# 05-multimodal-analogfrontend.net
KiCad netlist of a schematic drawn in Altium Designer
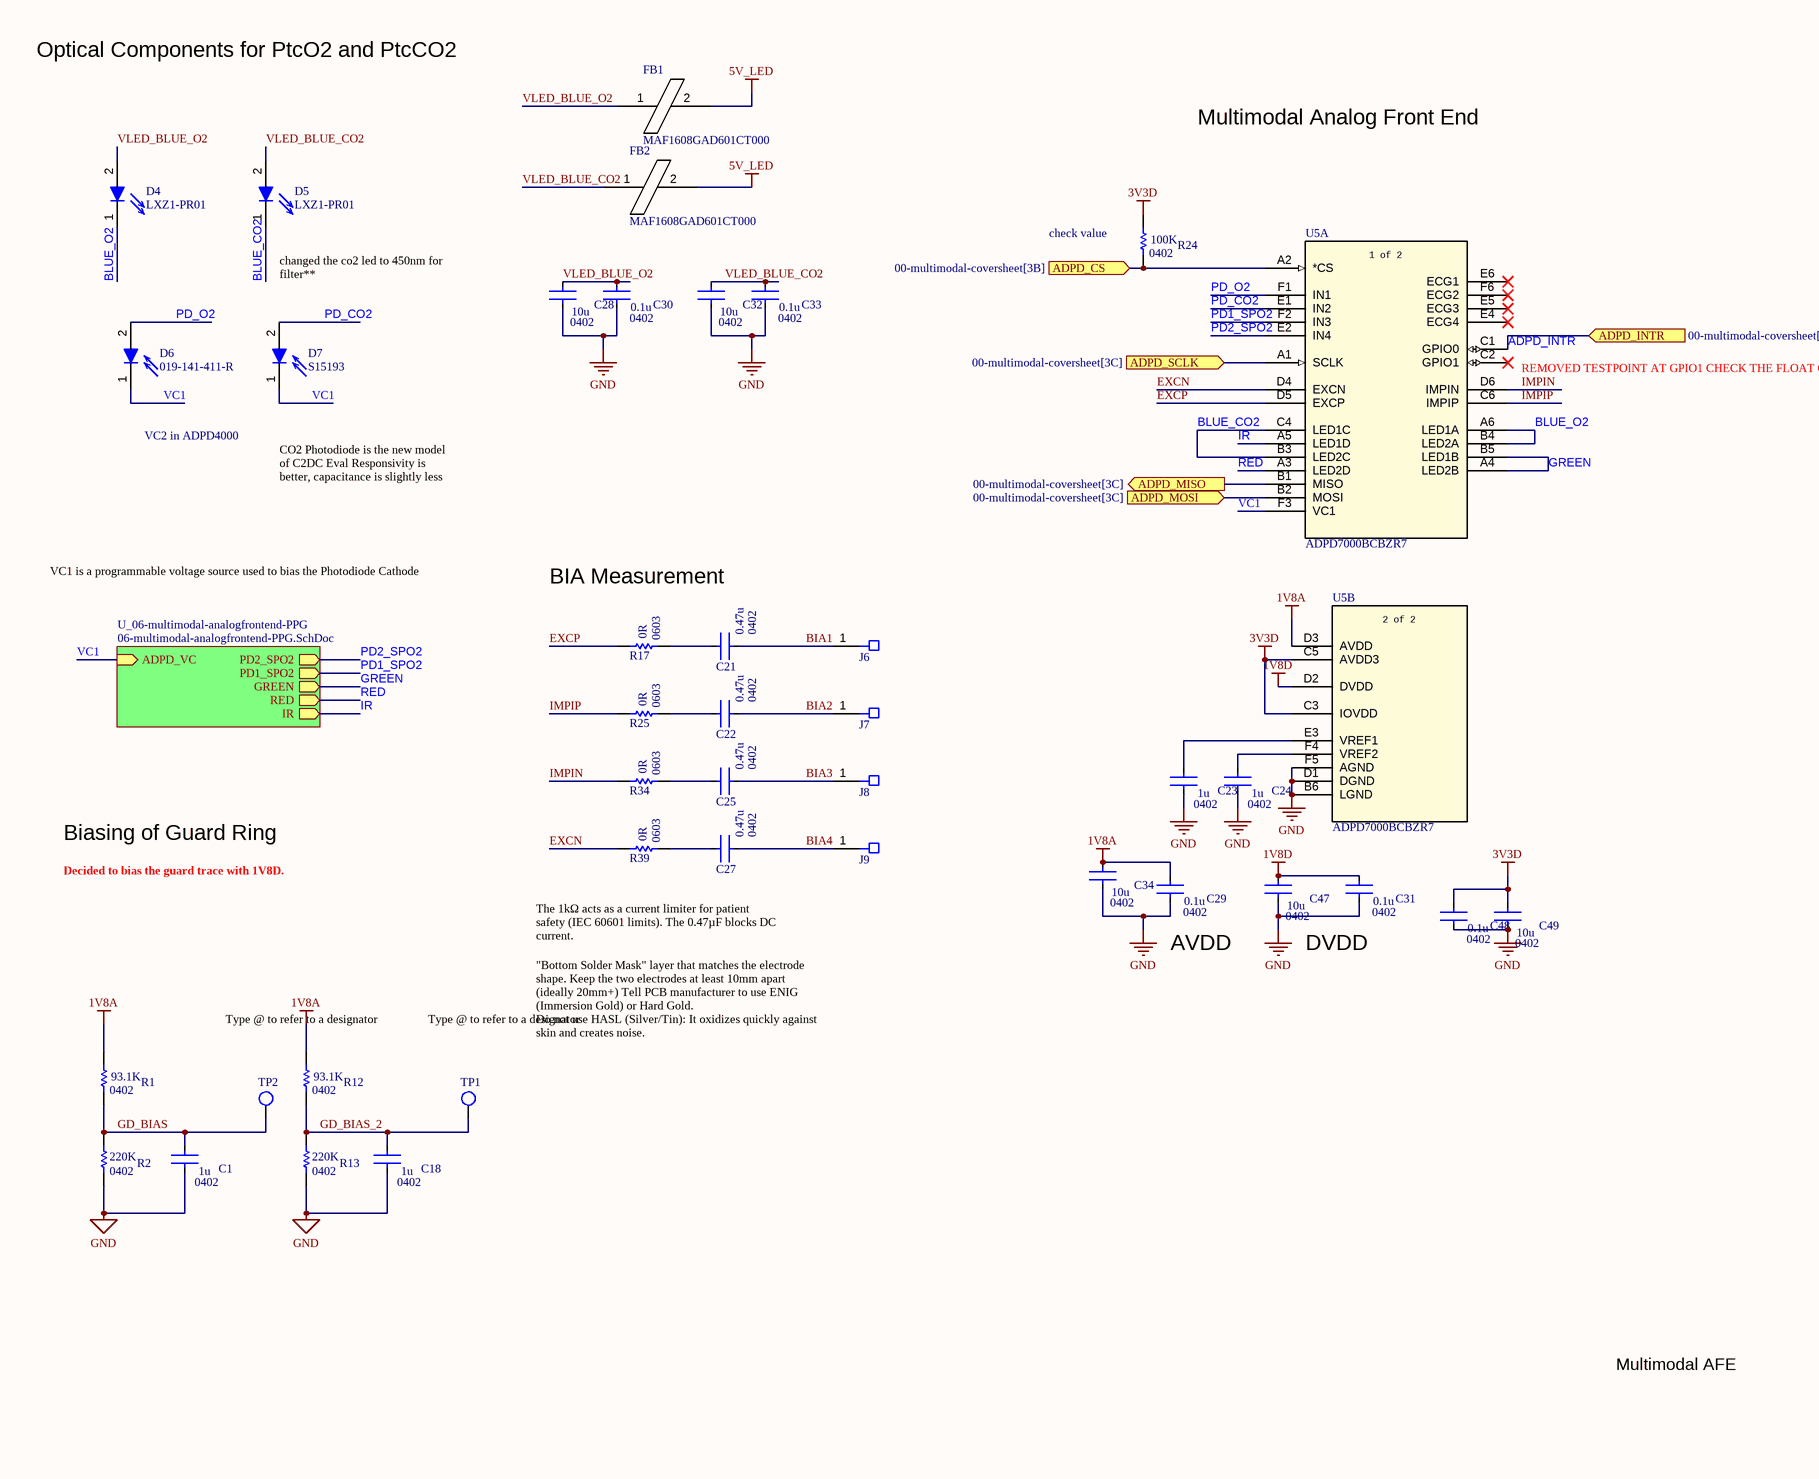
[diagram p0: 05-multimodal-analogfrontend.SchDoc, left]
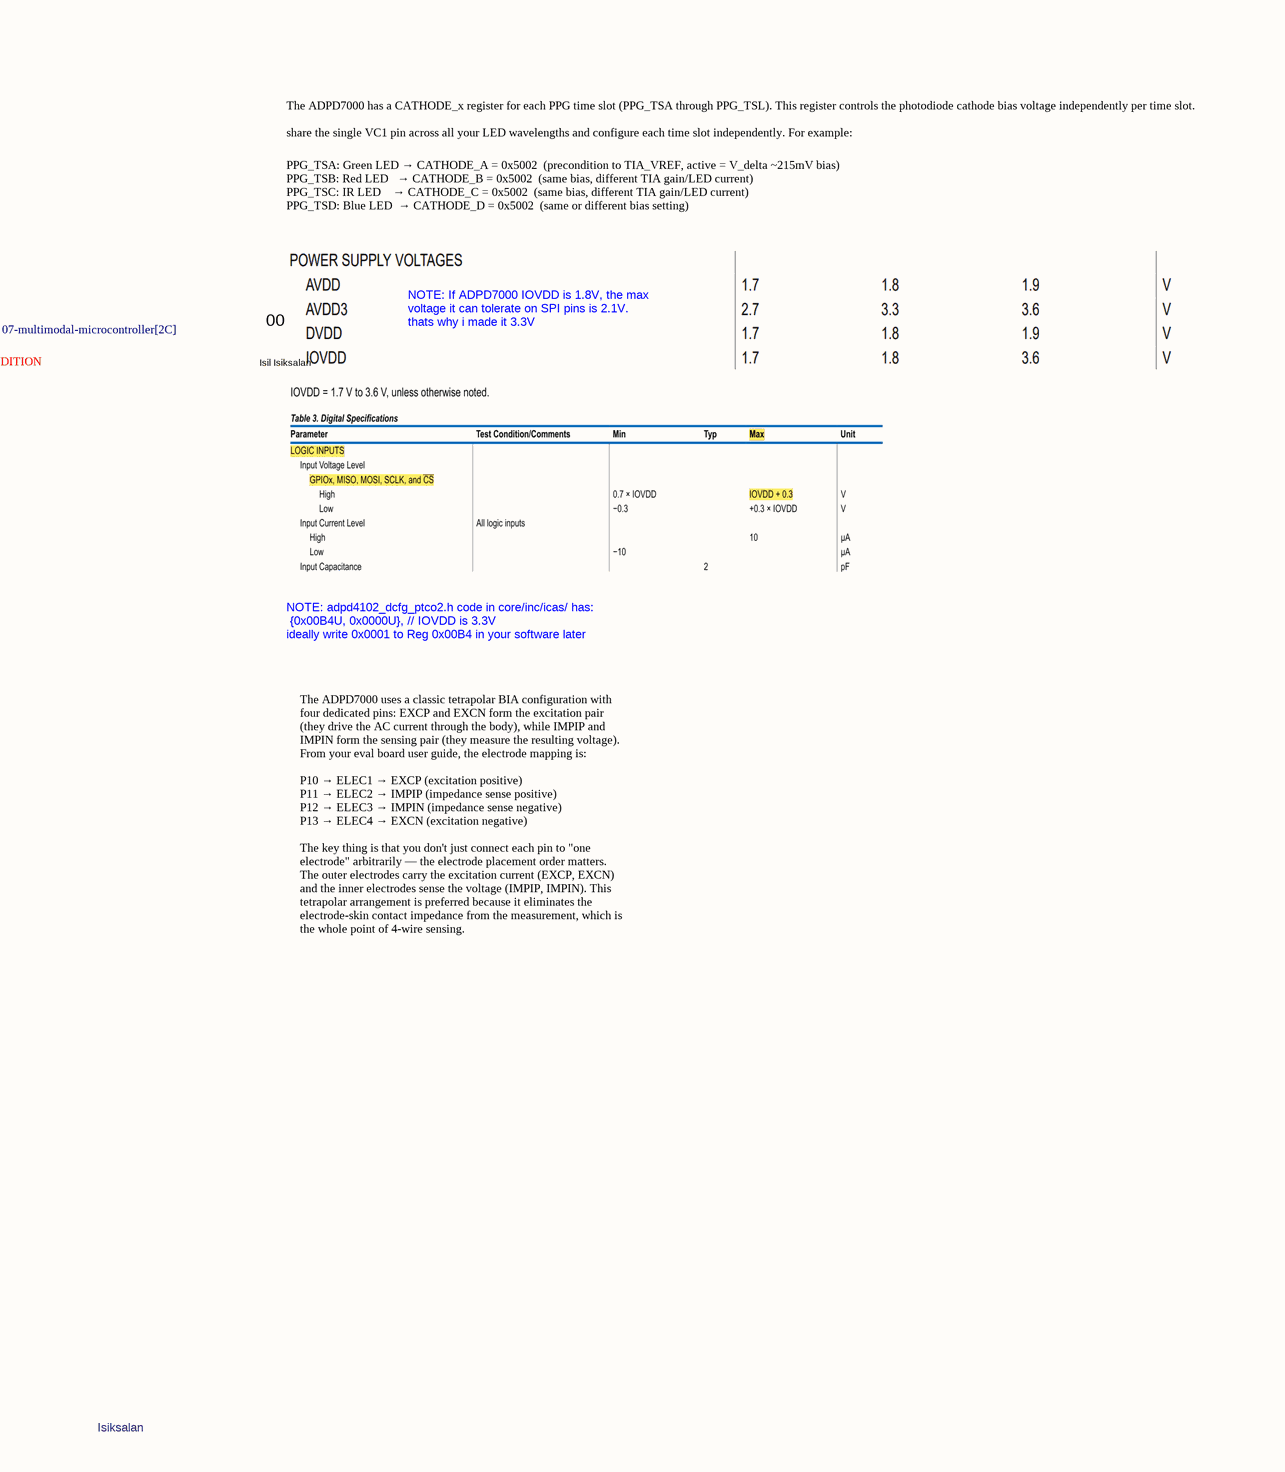
[diagram p1: 05-multimodal-analogfrontend.SchDoc, right]

(export (version "E")
  (design (tool "Eeschema 10.0.6"))
  (components
    (comp (ref "C1")
      (value "C1005X5R1V105K050BC")
      (footprint "CAPTDK0402")
      (description "CAP CER 1UF 35V X5R 0402")
      (libsource (lib "multimodal") (part "C1005X5R1V105K050BC"))
    )
    (comp (ref "C18")
      (value "C1005X5R1V105K050BC")
      (footprint "CAPTDK0402")
      (description "CAP CER 1UF 35V X5R 0402")
      (libsource (lib "multimodal") (part "C1005X5R1V105K050BC"))
    )
    (comp (ref "C21")
      (value "GRM155R60J474KE19D")
      (footprint "CAPTDK0402")
      (description "CAP CER 0.47UF 6.3V X5R 0402")
      (libsource (lib "multimodal") (part "GRM155R60J474KE19D"))
    )
    (comp (ref "C22")
      (value "GRM155R60J474KE19D")
      (footprint "CAPTDK0402")
      (description "CAP CER 0.47UF 6.3V X5R 0402")
      (libsource (lib "multimodal") (part "GRM155R60J474KE19D"))
    )
    (comp (ref "C23")
      (value "C1005X5R1V105K050BC")
      (footprint "CAPTDK0402")
      (description "CAP CER 1UF 35V X5R 0402")
      (libsource (lib "multimodal") (part "C1005X5R1V105K050BC"))
    )
    (comp (ref "C24")
      (value "C1005X5R1V105K050BC")
      (footprint "CAPTDK0402")
      (description "CAP CER 1UF 35V X5R 0402")
      (libsource (lib "multimodal") (part "C1005X5R1V105K050BC"))
    )
    (comp (ref "C25")
      (value "GRM155R60J474KE19D")
      (footprint "CAPTDK0402")
      (description "CAP CER 0.47UF 6.3V X5R 0402")
      (libsource (lib "multimodal") (part "GRM155R60J474KE19D"))
    )
    (comp (ref "C27")
      (value "GRM155R60J474KE19D")
      (footprint "CAPTDK0402")
      (description "CAP CER 0.47UF 6.3V X5R 0402")
      (libsource (lib "multimodal") (part "GRM155R60J474KE19D"))
    )
    (comp (ref "C28")
      (value "0402W106M6R3HI")
      (footprint "CAPTDK0402")
      (description "CAP SMD,0402,X5R,10UF,20%,6.3V")
      (libsource (lib "multimodal") (part "0402W106M6R3HI"))
    )
    (comp (ref "C29")
      (value "C1005X7R1H104K050BB")
      (footprint "CAPTDK0402")
      (description "CAP CER 0.1UF 50V X7R 0402")
      (libsource (lib "multimodal") (part "C1005X7R1H104K050BB"))
    )
    (comp (ref "C30")
      (value "C1005X7R1H104K050BB")
      (footprint "CAPTDK0402")
      (description "CAP CER 0.1UF 50V X7R 0402")
      (libsource (lib "multimodal") (part "C1005X7R1H104K050BB"))
    )
    (comp (ref "C31")
      (value "C1005X7R1H104K050BB")
      (footprint "CAPTDK0402")
      (description "CAP CER 0.1UF 50V X7R 0402")
      (libsource (lib "multimodal") (part "C1005X7R1H104K050BB"))
    )
    (comp (ref "C32")
      (value "0402W106M6R3HI")
      (footprint "CAPTDK0402")
      (description "CAP SMD,0402,X5R,10UF,20%,6.3V")
      (libsource (lib "multimodal") (part "0402W106M6R3HI"))
    )
    (comp (ref "C33")
      (value "C1005X7R1H104K050BB")
      (footprint "CAPTDK0402")
      (description "CAP CER 0.1UF 50V X7R 0402")
      (libsource (lib "multimodal") (part "C1005X7R1H104K050BB"))
    )
    (comp (ref "C34")
      (value "GRM155R61A106ME11D")
      (footprint "CAPTDK0402")
      (description "CAP CER 10UF 10V X5R 0402")
      (libsource (lib "multimodal") (part "GRM155R61A106ME11D"))
    )
    (comp (ref "C47")
      (value "GRM155R61A106ME11D")
      (footprint "CAPTDK0402")
      (description "CAP CER 10UF 10V X5R 0402")
      (libsource (lib "multimodal") (part "GRM155R61A106ME11D"))
    )
    (comp (ref "C48")
      (value "C1005X7R1H104K050BB")
      (footprint "CAPTDK0402")
      (description "CAP CER 0.1UF 50V X7R 0402")
      (libsource (lib "multimodal") (part "C1005X7R1H104K050BB"))
    )
    (comp (ref "C49")
      (value "GRM155R61A106ME11D")
      (footprint "CAPTDK0402")
      (description "CAP CER 10UF 10V X5R 0402")
      (libsource (lib "multimodal") (part "GRM155R61A106ME11D"))
    )
    (comp (ref "D4")
      (value "LXZ1-PR01")
      (footprint "LXZ1-PR01")
      (description "LED LUXEON Z RYL BLUE 450NM 2SMD")
      (fields (field (name "MANUFACTURER") "Philips Lumileds"))
      (libsource (lib "multimodal") (part "LXZ1-PR01"))
    )
    (comp (ref "D5")
      (value "LXZ1-PR01")
      (footprint "LXZ1-PR01")
      (description "LED LUXEON Z RYL BLUE 450NM 2SMD")
      (fields (field (name "MANUFACTURER") "Philips Lumileds"))
      (libsource (lib "multimodal") (part "LXZ1-PR01"))
    )
    (comp (ref "D6")
      (value "019-141-411-R")
      (footprint "RED-PD")
      (description "PHOTODIODE RED MICRO SMT")
      (libsource (lib "multimodal") (part "019-141-411-R"))
    )
    (comp (ref "D7")
      (value "S15193")
      (footprint "S15193")
      (description "PHOTODIODE PIN 380 NM-1000 NM 20V 0.64 A/W SMD")
      (fields (field (name "MANUFACTURER") "Hamamatsu"))
      (libsource (lib "multimodal") (part "S15193"))
    )
    (comp (ref "FB1")
      (value "MAF1608GAD601CT000")
      (footprint "INDMURT0603")
      (description "FERRITE BEAD 120 OHM 0603 1LN")
      (libsource (lib "multimodal") (part "MAF1608GAD601CT000"))
    )
    (comp (ref "FB2")
      (value "MAF1608GAD601CT000")
      (footprint "INDMURT0603")
      (description "FERRITE BEAD 120 OHM 0603 1LN")
      (libsource (lib "multimodal") (part "MAF1608GAD601CT000"))
    )
    (comp (ref "J6")
      (value "electrode")
      (footprint "electrode")
      (description "one pad opening")
      (libsource (lib "multimodal") (part "electrode"))
    )
    (comp (ref "J7")
      (value "electrode")
      (footprint "electrode")
      (description "one pad opening")
      (libsource (lib "multimodal") (part "electrode"))
    )
    (comp (ref "J8")
      (value "electrode")
      (footprint "electrode")
      (description "one pad opening")
      (libsource (lib "multimodal") (part "electrode"))
    )
    (comp (ref "J9")
      (value "electrode")
      (footprint "electrode")
      (description "one pad opening")
      (libsource (lib "multimodal") (part "electrode"))
    )
    (comp (ref "R1")
      (value "RMCF0402FT93K1")
      (footprint "RES-STACK-POLE-0402")
      (description "RES 93.1K OHM 1% 1/16W 0402")
      (fields
        (field (name "MANUFACTURER_PART_NUMBER") "RMCF0603FT80K6")
        (field (name "COPYRIGHT") "Copyright (C) 2022 Ultra Librarian. All rights reserved.")
      )
      (libsource (lib "multimodal") (part "RMCF0402FT93K1"))
    )
    (comp (ref "R2")
      (value "RMCF0402FT220K")
      (footprint "RES-STACK-POLE-0402")
      (description "RES 220K OHM 1% 1/16W 0402")
      (libsource (lib "multimodal") (part "RMCF0402FT220K"))
    )
    (comp (ref "R12")
      (value "RMCF0402FT93K1")
      (footprint "RES-STACK-POLE-0402")
      (description "RES 93.1K OHM 1% 1/16W 0402")
      (fields
        (field (name "MANUFACTURER_PART_NUMBER") "RMCF0603FT80K6")
        (field (name "COPYRIGHT") "Copyright (C) 2022 Ultra Librarian. All rights reserved.")
      )
      (libsource (lib "multimodal") (part "RMCF0402FT93K1"))
    )
    (comp (ref "R13")
      (value "RMCF0402FT220K")
      (footprint "RES-STACK-POLE-0402")
      (description "RES 220K OHM 1% 1/16W 0402")
      (libsource (lib "multimodal") (part "RMCF0402FT220K"))
    )
    (comp (ref "R17")
      (value "RMCF0603ZT0R00")
      (footprint "RES-STACK-POLE-0603")
      (description "RES 0 OHM JUMPER 1/10W 0603")
      (libsource (lib "multimodal") (part "RMCF0603ZT0R00"))
    )
    (comp (ref "R24")
      (value "RMCF0402FT100K")
      (footprint "RES-STACK-POLE-0402")
      (description "RES 100K OHM 1% 1/16W 0402")
      (libsource (lib "multimodal") (part "RMCF0402FT100K"))
    )
    (comp (ref "R25")
      (value "RMCF0603ZT0R00")
      (footprint "RES-STACK-POLE-0603")
      (description "RES 0 OHM JUMPER 1/10W 0603")
      (libsource (lib "multimodal") (part "RMCF0603ZT0R00"))
    )
    (comp (ref "R34")
      (value "RMCF0603ZT0R00")
      (footprint "RES-STACK-POLE-0603")
      (description "RES 0 OHM JUMPER 1/10W 0603")
      (libsource (lib "multimodal") (part "RMCF0603ZT0R00"))
    )
    (comp (ref "R39")
      (value "RMCF0603ZT0R00")
      (footprint "RES-STACK-POLE-0603")
      (description "RES 0 OHM JUMPER 1/10W 0603")
      (libsource (lib "multimodal") (part "RMCF0603ZT0R00"))
    )
    (comp (ref "TP1")
      (value "TESTPOINT_S")
      (footprint "TESTPOINT_S")
      (description "Testpoint Surface Pad")
      (libsource (lib "tom0002") (part "TESTPOINT_S"))
    )
    (comp (ref "TP2")
      (value "TESTPOINT_S")
      (footprint "TESTPOINT_S")
      (description "Testpoint Surface Pad")
      (libsource (lib "tom0002") (part "TESTPOINT_S"))
    )
    (comp (ref "U5")
      (value "ADPD7000BCBZR7")
      (footprint "ADPD7001_36-WLCSP")
      (description "Multimodal Sensor Front End")
      (fields (field (name "COPYRIGHT") "Copyright (C) 2026 Ultra Librarian. All rights reserved."))
      (libsource (lib "multimodal") (part "ADPD7000BCBZR7"))
    )
  )
  (nets
    (net (code "1") (name "/ADPD_CS") (class "Default")
      (node (ref "R24") (pin "1") (pinfunction "1_1") (pintype "passive"))
      (node (ref "U5") (pin "A2") (pinfunction "*CS_A2") (pintype "input"))
    )
    (net (code "2") (name "/ADPD_INTR") (class "Default")
      (node (ref "U5") (pin "C1") (pinfunction "GPIO0_C1") (pintype "bidirectional"))
    )
    (net (code "3") (name "/ADPD_MISO") (class "Default")
      (node (ref "U5") (pin "B1") (pinfunction "MISO_B1") (pintype "passive"))
    )
    (net (code "4") (name "/ADPD_MOSI") (class "Default")
      (node (ref "U5") (pin "B2") (pinfunction "MOSI_B2") (pintype "passive"))
    )
    (net (code "5") (name "/ADPD_SCLK") (class "Default")
      (node (ref "U5") (pin "A1") (pinfunction "SCLK_A1") (pintype "input"))
    )
    (net (code "6") (name "/BIA1") (class "Default")
      (node (ref "C21") (pin "2") (pinfunction "2_2") (pintype "passive"))
      (node (ref "J6") (pin "1") (pinfunction "1_1") (pintype "passive"))
    )
    (net (code "7") (name "/BIA2") (class "Default")
      (node (ref "C22") (pin "2") (pinfunction "2_2") (pintype "passive"))
      (node (ref "J7") (pin "1") (pinfunction "1_1") (pintype "passive"))
    )
    (net (code "8") (name "/BIA3") (class "Default")
      (node (ref "C25") (pin "2") (pinfunction "2_2") (pintype "passive"))
      (node (ref "J8") (pin "1") (pinfunction "1_1") (pintype "passive"))
    )
    (net (code "9") (name "/BIA4") (class "Default")
      (node (ref "C27") (pin "2") (pinfunction "2_2") (pintype "passive"))
      (node (ref "J9") (pin "1") (pinfunction "1_1") (pintype "passive"))
    )
    (net (code "10") (name "/BLUE_CO2") (class "Default")
      (node (ref "D5") (pin "1") (pintype "passive"))
      (node (ref "U5") (pin "B3") (pinfunction "LED2C_B3") (pintype "passive"))
      (node (ref "U5") (pin "C4") (pinfunction "LED1C_C4") (pintype "passive"))
    )
    (net (code "11") (name "/BLUE_O2") (class "Default")
      (node (ref "D4") (pin "1") (pintype "passive"))
      (node (ref "U5") (pin "A6") (pinfunction "LED1A_A6") (pintype "passive"))
      (node (ref "U5") (pin "B4") (pinfunction "LED2A_B4") (pintype "passive"))
    )
    (net (code "12") (name "/EXCN") (class "Default")
      (node (ref "R39") (pin "2") (pinfunction "2_2") (pintype "passive"))
      (node (ref "U5") (pin "D4") (pinfunction "EXCN_D4") (pintype "passive"))
    )
    (net (code "13") (name "/EXCP") (class "Default")
      (node (ref "R17") (pin "2") (pinfunction "2_2") (pintype "passive"))
      (node (ref "U5") (pin "D5") (pinfunction "EXCP_D5") (pintype "passive"))
    )
    (net (code "14") (name "/GD_BIAS") (class "Default")
      (node (ref "C1") (pin "1") (pinfunction "1_1") (pintype "passive"))
      (node (ref "R1") (pin "1") (pinfunction "1_1") (pintype "passive"))
      (node (ref "R2") (pin "2") (pinfunction "2_2") (pintype "passive"))
      (node (ref "TP2") (pin "1") (pinfunction "1_1") (pintype "passive"))
    )
    (net (code "15") (name "/GD_BIAS_2") (class "Default")
      (node (ref "C18") (pin "1") (pinfunction "1_1") (pintype "passive"))
      (node (ref "R12") (pin "1") (pinfunction "1_1") (pintype "passive"))
      (node (ref "R13") (pin "2") (pinfunction "2_2") (pintype "passive"))
      (node (ref "TP1") (pin "1") (pinfunction "1_1") (pintype "passive"))
    )
    (net (code "16") (name "/GREEN") (class "Default")
      (node (ref "U5") (pin "A4") (pinfunction "LED2B_A4") (pintype "passive"))
      (node (ref "U5") (pin "B5") (pinfunction "LED1B_B5") (pintype "passive"))
    )
    (net (code "17") (name "/IMPIN") (class "Default")
      (node (ref "R34") (pin "2") (pinfunction "2_2") (pintype "passive"))
      (node (ref "U5") (pin "D6") (pinfunction "IMPIN_D6") (pintype "passive"))
    )
    (net (code "18") (name "/IMPIP") (class "Default")
      (node (ref "R25") (pin "2") (pinfunction "2_2") (pintype "passive"))
      (node (ref "U5") (pin "C6") (pinfunction "IMPIP_C6") (pintype "passive"))
    )
    (net (code "19") (name "/IR") (class "Default")
      (node (ref "U5") (pin "A5") (pinfunction "LED1D_A5") (pintype "passive"))
    )
    (net (code "20") (name "/PD1_SPO2") (class "Default")
      (node (ref "U5") (pin "F2") (pinfunction "IN3_F2") (pintype "passive"))
    )
    (net (code "21") (name "/PD2_SPO2") (class "Default")
      (node (ref "U5") (pin "E2") (pinfunction "IN4_E2") (pintype "passive"))
    )
    (net (code "22") (name "/PD_CO2") (class "Default")
      (node (ref "D7") (pin "2") (pintype "passive"))
      (node (ref "U5") (pin "E1") (pinfunction "IN2_E1") (pintype "passive"))
    )
    (net (code "23") (name "/PD_O2") (class "Default")
      (node (ref "D6") (pin "2") (pintype "passive"))
      (node (ref "U5") (pin "F1") (pinfunction "IN1_F1") (pintype "passive"))
    )
    (net (code "24") (name "/RED") (class "Default")
      (node (ref "U5") (pin "A3") (pinfunction "LED2D_A3") (pintype "passive"))
    )
    (net (code "25") (name "/VC1") (class "Default")
      (node (ref "D6") (pin "1") (pintype "passive"))
      (node (ref "D7") (pin "1") (pintype "passive"))
      (node (ref "U5") (pin "F3") (pinfunction "VC1_F3") (pintype "passive"))
    )
    (net (code "26") (name "/VLED_BLUE_CO2") (class "Default")
      (node (ref "C32") (pin "1") (pinfunction "1_1") (pintype "passive"))
      (node (ref "C33") (pin "1") (pinfunction "1_1") (pintype "passive"))
      (node (ref "D5") (pin "2") (pintype "passive"))
      (node (ref "FB2") (pin "1") (pinfunction "1_1") (pintype "passive"))
    )
    (net (code "27") (name "/VLED_BLUE_O2") (class "Default")
      (node (ref "C28") (pin "1") (pinfunction "1_1") (pintype "passive"))
      (node (ref "C30") (pin "1") (pinfunction "1_1") (pintype "passive"))
      (node (ref "D4") (pin "2") (pintype "passive"))
      (node (ref "FB1") (pin "1") (pinfunction "1_1") (pintype "passive"))
    )
    (net (code "28") (name "1V8A") (class "Default")
      (node (ref "C29") (pin "1") (pinfunction "1_1") (pintype "passive"))
      (node (ref "C34") (pin "1") (pinfunction "1_1") (pintype "passive"))
      (node (ref "R1") (pin "2") (pinfunction "2_2") (pintype "passive"))
      (node (ref "R12") (pin "2") (pinfunction "2_2") (pintype "passive"))
      (node (ref "U5") (pin "D3") (pinfunction "AVDD_D3") (pintype "power_in"))
    )
    (net (code "29") (name "1V8D") (class "Default")
      (node (ref "C31") (pin "1") (pinfunction "1_1") (pintype "passive"))
      (node (ref "C47") (pin "1") (pinfunction "1_1") (pintype "passive"))
      (node (ref "U5") (pin "D2") (pinfunction "DVDD_D2") (pintype "power_in"))
    )
    (net (code "30") (name "3V3D") (class "Default")
      (node (ref "C48") (pin "1") (pinfunction "1_1") (pintype "passive"))
      (node (ref "C49") (pin "1") (pinfunction "1_1") (pintype "passive"))
      (node (ref "R24") (pin "2") (pinfunction "2_2") (pintype "passive"))
      (node (ref "U5") (pin "C3") (pinfunction "IOVDD_C3") (pintype "power_in"))
      (node (ref "U5") (pin "C5") (pinfunction "AVDD3_C5") (pintype "power_in"))
    )
    (net (code "31") (name "5V_LED") (class "Default")
      (node (ref "FB1") (pin "2") (pinfunction "2_2") (pintype "passive"))
      (node (ref "FB2") (pin "2") (pinfunction "2_2") (pintype "passive"))
    )
    (net (code "32") (name "GND") (class "Default")
      (node (ref "C1") (pin "2") (pinfunction "2_2") (pintype "passive"))
      (node (ref "C18") (pin "2") (pinfunction "2_2") (pintype "passive"))
      (node (ref "C23") (pin "2") (pinfunction "2_2") (pintype "passive"))
      (node (ref "C24") (pin "2") (pinfunction "2_2") (pintype "passive"))
      (node (ref "C28") (pin "2") (pinfunction "2_2") (pintype "passive"))
      (node (ref "C29") (pin "2") (pinfunction "2_2") (pintype "passive"))
      (node (ref "C30") (pin "2") (pinfunction "2_2") (pintype "passive"))
      (node (ref "C31") (pin "2") (pinfunction "2_2") (pintype "passive"))
      (node (ref "C32") (pin "2") (pinfunction "2_2") (pintype "passive"))
      (node (ref "C33") (pin "2") (pinfunction "2_2") (pintype "passive"))
      (node (ref "C34") (pin "2") (pinfunction "2_2") (pintype "passive"))
      (node (ref "C47") (pin "2") (pinfunction "2_2") (pintype "passive"))
      (node (ref "C48") (pin "2") (pinfunction "2_2") (pintype "passive"))
      (node (ref "C49") (pin "2") (pinfunction "2_2") (pintype "passive"))
      (node (ref "R13") (pin "1") (pinfunction "1_1") (pintype "passive"))
      (node (ref "R2") (pin "1") (pinfunction "1_1") (pintype "passive"))
      (node (ref "U5") (pin "B6") (pinfunction "LGND_B6") (pintype "power_in"))
      (node (ref "U5") (pin "D1") (pinfunction "DGND_D1") (pintype "power_in"))
      (node (ref "U5") (pin "F5") (pinfunction "AGND_F5") (pintype "power_in"))
    )
    (net (code "33") (name "Net-(C21-Pad1)") (class "Default")
      (node (ref "C21") (pin "1") (pinfunction "1_1") (pintype "passive"))
      (node (ref "R17") (pin "1") (pinfunction "1_1") (pintype "passive"))
    )
    (net (code "34") (name "Net-(C22-Pad1)") (class "Default")
      (node (ref "C22") (pin "1") (pinfunction "1_1") (pintype "passive"))
      (node (ref "R25") (pin "1") (pinfunction "1_1") (pintype "passive"))
    )
    (net (code "35") (name "Net-(C25-Pad1)") (class "Default")
      (node (ref "C25") (pin "1") (pinfunction "1_1") (pintype "passive"))
      (node (ref "R34") (pin "1") (pinfunction "1_1") (pintype "passive"))
    )
    (net (code "36") (name "Net-(C27-Pad1)") (class "Default")
      (node (ref "C27") (pin "1") (pinfunction "1_1") (pintype "passive"))
      (node (ref "R39") (pin "1") (pinfunction "1_1") (pintype "passive"))
    )
    (net (code "37") (name "Net-(U5B-VREF1)") (class "Default")
      (node (ref "C23") (pin "1") (pinfunction "1_1") (pintype "passive"))
      (node (ref "U5") (pin "E3") (pinfunction "VREF1_E3") (pintype "passive"))
    )
    (net (code "38") (name "Net-(U5B-VREF2)") (class "Default")
      (node (ref "C24") (pin "1") (pinfunction "1_1") (pintype "passive"))
      (node (ref "U5") (pin "F4") (pinfunction "VREF2_F4") (pintype "passive"))
    )
    (net (code "39") (name "unconnected-(U5A-ECG1-PadE6)") (class "Default")
      (node (ref "U5") (pin "E6") (pinfunction "ECG1_E6") (pintype "passive+no_connect"))
    )
    (net (code "40") (name "unconnected-(U5A-ECG2-PadF6)") (class "Default")
      (node (ref "U5") (pin "F6") (pinfunction "ECG2_F6") (pintype "passive+no_connect"))
    )
    (net (code "41") (name "unconnected-(U5A-ECG3-PadE5)") (class "Default")
      (node (ref "U5") (pin "E5") (pinfunction "ECG3_E5") (pintype "passive+no_connect"))
    )
    (net (code "42") (name "unconnected-(U5A-ECG4-PadE4)") (class "Default")
      (node (ref "U5") (pin "E4") (pinfunction "ECG4_E4") (pintype "passive+no_connect"))
    )
    (net (code "43") (name "unconnected-(U5A-GPIO1-PadC2)") (class "Default")
      (node (ref "U5") (pin "C2") (pinfunction "GPIO1_C2") (pintype "bidirectional+no_connect"))
    )
  )
)
